# motor_board.net
KiCad netlist of a schematic drawn in EAGLE
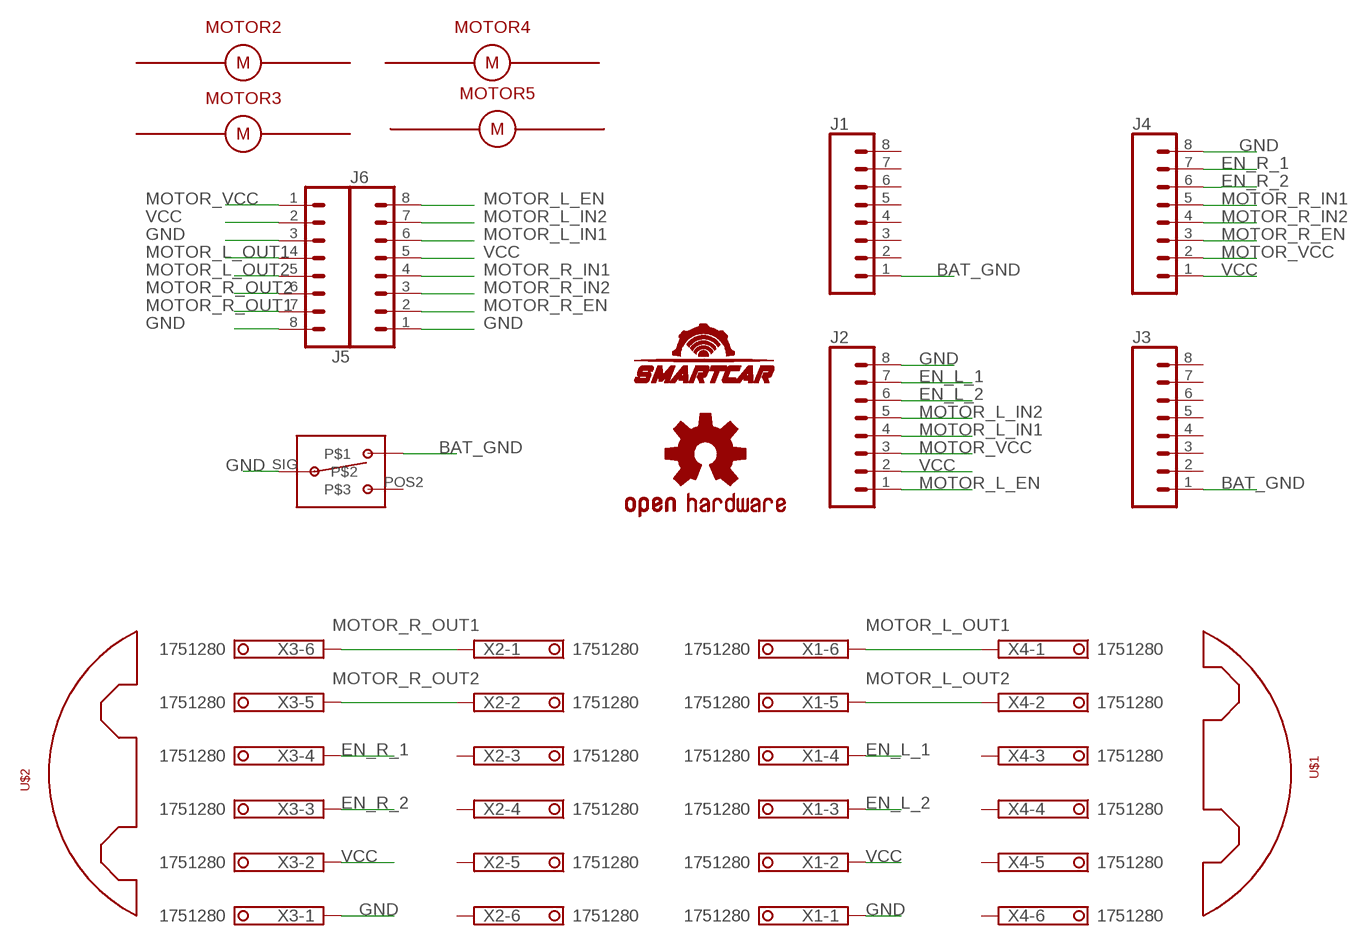
[diagram p0: schematic, sheet 1]

(export (version "E")
  (design (tool "Eeschema 10.0.6"))
  (components
    (comp (ref "J1")
      (value "CONN_08NO_SILK_FEMALE_PTH")
      (footprint "eagle-import:1X08_NO_SILK")
      (libsource (lib "eagle-import") (part "CONN_08NO_SILK_FEMALE_PTH"))
    )
    (comp (ref "J2")
      (value "CONN_08NO_SILK_FEMALE_PTH")
      (footprint "eagle-import:1X08_NO_SILK")
      (libsource (lib "eagle-import") (part "CONN_08NO_SILK_FEMALE_PTH"))
    )
    (comp (ref "J3")
      (value "CONN_08NO_SILK_FEMALE_PTH")
      (footprint "eagle-import:1X08_NO_SILK")
      (libsource (lib "eagle-import") (part "CONN_08NO_SILK_FEMALE_PTH"))
    )
    (comp (ref "J4")
      (value "CONN_08NO_SILK_FEMALE_PTH")
      (footprint "eagle-import:1X08_NO_SILK")
      (libsource (lib "eagle-import") (part "CONN_08NO_SILK_FEMALE_PTH"))
    )
    (comp (ref "J5")
      (value "CONN_08\"")
      (footprint "eagle-import:1X08")
      (libsource (lib "eagle-import") (part "CONN_08{dblquote}"))
    )
    (comp (ref "J6")
      (value "CONN_08\"")
      (footprint "eagle-import:1X08")
      (libsource (lib "eagle-import") (part "CONN_08{dblquote}"))
    )
    (comp (ref "LOGO1")
      (value "OSHW-LOGOL")
      (footprint "eagle-import:OSHW-LOGO-L")
      (libsource (lib "eagle-import") (part "OSHW-LOGOL"))
    )
    (comp (ref "MOTOR2")
      (value "SMARTCAR_MOTOR")
      (footprint "eagle-import:SMARTCAR_MOTOR_MOUNT_HOLES")
      (libsource (lib "eagle-import") (part "SMARTCAR_MOTOR"))
    )
    (comp (ref "MOTOR3")
      (value "SMARTCAR_MOTOR")
      (footprint "eagle-import:SMARTCAR_MOTOR_MOUNT_HOLES")
      (libsource (lib "eagle-import") (part "SMARTCAR_MOTOR"))
    )
    (comp (ref "MOTOR4")
      (value "SMARTCAR_MOTOR")
      (footprint "eagle-import:SMARTCAR_MOTOR_MOUNT_HOLES")
      (libsource (lib "eagle-import") (part "SMARTCAR_MOTOR"))
    )
    (comp (ref "MOTOR5")
      (value "SMARTCAR_MOTOR")
      (footprint "eagle-import:SMARTCAR_MOTOR_MOUNT_HOLES")
      (libsource (lib "eagle-import") (part "SMARTCAR_MOTOR"))
    )
    (comp (ref "SMRTCR1")
      (value "SMARTCAR_LOGOMEDIUM")
      (footprint "eagle-import:SMARTCAR_LOGO_MEDIUM")
      (libsource (lib "eagle-import") (part "SMARTCAR_LOGOMEDIUM"))
    )
    (comp (ref "SW1")
      (value "SPDT-HIGH-AMP-SWITCHPTH")
      (footprint "eagle-import:SPDT-0.2-THICK-PINS")
      (libsource (lib "eagle-import") (part "SPDT-HIGH-AMP-SWITCHPTH"))
    )
    (comp (ref "U$1")
      (value "BUMPER_020522_SCREWS")
      (footprint "eagle-import:BUMPER_2_SCREWS_NARROW")
      (libsource (lib "eagle-import") (part "BUMPER_020522_SCREWS"))
    )
    (comp (ref "U$2")
      (value "BUMPER_020522_SCREWS")
      (footprint "eagle-import:BUMPER_2_SCREWS_NARROW")
      (libsource (lib "eagle-import") (part "BUMPER_020522_SCREWS"))
    )
    (comp (ref "X1")
      (value "1751280")
      (footprint "eagle-import:1751280")
      (libsource (lib "eagle-import") (part "1751280"))
    )
    (comp (ref "X2")
      (value "1751280")
      (footprint "eagle-import:1751280")
      (libsource (lib "eagle-import") (part "1751280"))
    )
    (comp (ref "X3")
      (value "1751280")
      (footprint "eagle-import:1751280")
      (libsource (lib "eagle-import") (part "1751280"))
    )
    (comp (ref "X4")
      (value "1751280")
      (footprint "eagle-import:1751280")
      (libsource (lib "eagle-import") (part "1751280"))
    )
  )
  (nets
    (net (code "1") (name "/BAT_GND") (class "Default")
      (node (ref "J1") (pin "1") (pinfunction "1_1") (pintype "passive"))
      (node (ref "J3") (pin "1") (pinfunction "1_1") (pintype "passive"))
      (node (ref "SW1") (pin "POS1") (pinfunction "P$1_POS1") (pintype "bidirectional"))
    )
    (net (code "2") (name "/EN_L_1") (class "Default")
      (node (ref "J2") (pin "7") (pinfunction "7_7") (pintype "passive"))
      (node (ref "X1") (pin "4") (pinfunction "K_4") (pintype "passive"))
    )
    (net (code "3") (name "/EN_L_2") (class "Default")
      (node (ref "J2") (pin "6") (pinfunction "6_6") (pintype "passive"))
      (node (ref "X1") (pin "3") (pinfunction "K_3") (pintype "passive"))
    )
    (net (code "4") (name "/EN_R_1") (class "Default")
      (node (ref "J4") (pin "7") (pinfunction "7_7") (pintype "passive"))
      (node (ref "X3") (pin "4") (pinfunction "K_4") (pintype "passive"))
    )
    (net (code "5") (name "/EN_R_2") (class "Default")
      (node (ref "J4") (pin "6") (pinfunction "6_6") (pintype "passive"))
      (node (ref "X3") (pin "3") (pinfunction "K_3") (pintype "passive"))
    )
    (net (code "6") (name "/GND") (class "Default")
      (node (ref "J2") (pin "8") (pinfunction "8_8") (pintype "passive"))
      (node (ref "J4") (pin "8") (pinfunction "8_8") (pintype "passive"))
      (node (ref "J5") (pin "3") (pinfunction "3_3") (pintype "passive"))
      (node (ref "J5") (pin "8") (pinfunction "8_8") (pintype "passive"))
      (node (ref "J6") (pin "1") (pinfunction "1_1") (pintype "passive"))
      (node (ref "SW1") (pin "SIG") (pinfunction "P$2_SIG") (pintype "bidirectional"))
      (node (ref "X1") (pin "1") (pinfunction "K_1") (pintype "passive"))
      (node (ref "X3") (pin "1") (pinfunction "K_1") (pintype "passive"))
    )
    (net (code "7") (name "/MOTOR_L_EN") (class "Default")
      (node (ref "J2") (pin "1") (pinfunction "1_1") (pintype "passive"))
      (node (ref "J6") (pin "8") (pinfunction "8_8") (pintype "passive"))
    )
    (net (code "8") (name "/MOTOR_L_IN1") (class "Default")
      (node (ref "J2") (pin "4") (pinfunction "4_4") (pintype "passive"))
      (node (ref "J6") (pin "6") (pinfunction "6_6") (pintype "passive"))
    )
    (net (code "9") (name "/MOTOR_L_IN2") (class "Default")
      (node (ref "J2") (pin "5") (pinfunction "5_5") (pintype "passive"))
      (node (ref "J6") (pin "7") (pinfunction "7_7") (pintype "passive"))
    )
    (net (code "10") (name "/MOTOR_L_OUT1") (class "Default")
      (node (ref "J5") (pin "4") (pinfunction "4_4") (pintype "passive"))
      (node (ref "X1") (pin "6") (pinfunction "K_6") (pintype "passive"))
      (node (ref "X4") (pin "1") (pinfunction "K_1") (pintype "passive"))
    )
    (net (code "11") (name "/MOTOR_L_OUT2") (class "Default")
      (node (ref "J5") (pin "5") (pinfunction "5_5") (pintype "passive"))
      (node (ref "X1") (pin "5") (pinfunction "K_5") (pintype "passive"))
      (node (ref "X4") (pin "2") (pinfunction "K_2") (pintype "passive"))
    )
    (net (code "12") (name "/MOTOR_R_EN") (class "Default")
      (node (ref "J4") (pin "3") (pinfunction "3_3") (pintype "passive"))
      (node (ref "J6") (pin "2") (pinfunction "2_2") (pintype "passive"))
    )
    (net (code "13") (name "/MOTOR_R_IN1") (class "Default")
      (node (ref "J4") (pin "5") (pinfunction "5_5") (pintype "passive"))
      (node (ref "J6") (pin "4") (pinfunction "4_4") (pintype "passive"))
    )
    (net (code "14") (name "/MOTOR_R_IN2") (class "Default")
      (node (ref "J4") (pin "4") (pinfunction "4_4") (pintype "passive"))
      (node (ref "J6") (pin "3") (pinfunction "3_3") (pintype "passive"))
    )
    (net (code "15") (name "/MOTOR_R_OUT1") (class "Default")
      (node (ref "J5") (pin "7") (pinfunction "7_7") (pintype "passive"))
      (node (ref "X2") (pin "1") (pinfunction "K_1") (pintype "passive"))
      (node (ref "X3") (pin "6") (pinfunction "K_6") (pintype "passive"))
    )
    (net (code "16") (name "/MOTOR_R_OUT2") (class "Default")
      (node (ref "J5") (pin "6") (pinfunction "6_6") (pintype "passive"))
      (node (ref "X2") (pin "2") (pinfunction "K_2") (pintype "passive"))
      (node (ref "X3") (pin "5") (pinfunction "K_5") (pintype "passive"))
    )
    (net (code "17") (name "/MOTOR_VCC") (class "Default")
      (node (ref "J2") (pin "3") (pinfunction "3_3") (pintype "passive"))
      (node (ref "J4") (pin "2") (pinfunction "2_2") (pintype "passive"))
      (node (ref "J5") (pin "1") (pinfunction "1_1") (pintype "passive"))
    )
    (net (code "18") (name "/VCC") (class "Default")
      (node (ref "J2") (pin "2") (pinfunction "2_2") (pintype "passive"))
      (node (ref "J4") (pin "1") (pinfunction "1_1") (pintype "passive"))
      (node (ref "J5") (pin "2") (pinfunction "2_2") (pintype "passive"))
      (node (ref "J6") (pin "5") (pinfunction "5_5") (pintype "passive"))
      (node (ref "X1") (pin "2") (pinfunction "K_2") (pintype "passive"))
      (node (ref "X3") (pin "2") (pinfunction "K_2") (pintype "passive"))
    )
    (net (code "19") (name "unconnected-(J1-Pad2)") (class "Default")
      (node (ref "J1") (pin "2") (pinfunction "2_2") (pintype "passive"))
    )
    (net (code "20") (name "unconnected-(J1-Pad3)") (class "Default")
      (node (ref "J1") (pin "3") (pinfunction "3_3") (pintype "passive"))
    )
    (net (code "21") (name "unconnected-(J1-Pad4)") (class "Default")
      (node (ref "J1") (pin "4") (pinfunction "4_4") (pintype "passive"))
    )
    (net (code "22") (name "unconnected-(J1-Pad5)") (class "Default")
      (node (ref "J1") (pin "5") (pinfunction "5_5") (pintype "passive"))
    )
    (net (code "23") (name "unconnected-(J1-Pad6)") (class "Default")
      (node (ref "J1") (pin "6") (pinfunction "6_6") (pintype "passive"))
    )
    (net (code "24") (name "unconnected-(J1-Pad7)") (class "Default")
      (node (ref "J1") (pin "7") (pinfunction "7_7") (pintype "passive"))
    )
    (net (code "25") (name "unconnected-(J1-Pad8)") (class "Default")
      (node (ref "J1") (pin "8") (pinfunction "8_8") (pintype "passive"))
    )
    (net (code "26") (name "unconnected-(J3-Pad2)") (class "Default")
      (node (ref "J3") (pin "2") (pinfunction "2_2") (pintype "passive"))
    )
    (net (code "27") (name "unconnected-(J3-Pad3)") (class "Default")
      (node (ref "J3") (pin "3") (pinfunction "3_3") (pintype "passive"))
    )
    (net (code "28") (name "unconnected-(J3-Pad4)") (class "Default")
      (node (ref "J3") (pin "4") (pinfunction "4_4") (pintype "passive"))
    )
    (net (code "29") (name "unconnected-(J3-Pad5)") (class "Default")
      (node (ref "J3") (pin "5") (pinfunction "5_5") (pintype "passive"))
    )
    (net (code "30") (name "unconnected-(J3-Pad6)") (class "Default")
      (node (ref "J3") (pin "6") (pinfunction "6_6") (pintype "passive"))
    )
    (net (code "31") (name "unconnected-(J3-Pad7)") (class "Default")
      (node (ref "J3") (pin "7") (pinfunction "7_7") (pintype "passive"))
    )
    (net (code "32") (name "unconnected-(J3-Pad8)") (class "Default")
      (node (ref "J3") (pin "8") (pinfunction "8_8") (pintype "passive"))
    )
    (net (code "33") (name "unconnected-(SW1-P$3-PadPOS2)") (class "Default")
      (node (ref "SW1") (pin "POS2") (pinfunction "P$3_POS2") (pintype "bidirectional"))
    )
    (net (code "34") (name "unconnected-(X2C-K-Pad3)") (class "Default")
      (node (ref "X2") (pin "3") (pinfunction "K_3") (pintype "passive"))
    )
    (net (code "35") (name "unconnected-(X2D-K-Pad4)") (class "Default")
      (node (ref "X2") (pin "4") (pinfunction "K_4") (pintype "passive"))
    )
    (net (code "36") (name "unconnected-(X2E-K-Pad5)") (class "Default")
      (node (ref "X2") (pin "5") (pinfunction "K_5") (pintype "passive"))
    )
    (net (code "37") (name "unconnected-(X2F-K-Pad6)") (class "Default")
      (node (ref "X2") (pin "6") (pinfunction "K_6") (pintype "passive"))
    )
    (net (code "38") (name "unconnected-(X4C-K-Pad3)") (class "Default")
      (node (ref "X4") (pin "3") (pinfunction "K_3") (pintype "passive"))
    )
    (net (code "39") (name "unconnected-(X4D-K-Pad4)") (class "Default")
      (node (ref "X4") (pin "4") (pinfunction "K_4") (pintype "passive"))
    )
    (net (code "40") (name "unconnected-(X4E-K-Pad5)") (class "Default")
      (node (ref "X4") (pin "5") (pinfunction "K_5") (pintype "passive"))
    )
    (net (code "41") (name "unconnected-(X4F-K-Pad6)") (class "Default")
      (node (ref "X4") (pin "6") (pinfunction "K_6") (pintype "passive"))
    )
  )
)
